# Teensy_Board_Connectors.net
KiCad netlist of a schematic drawn in EAGLE
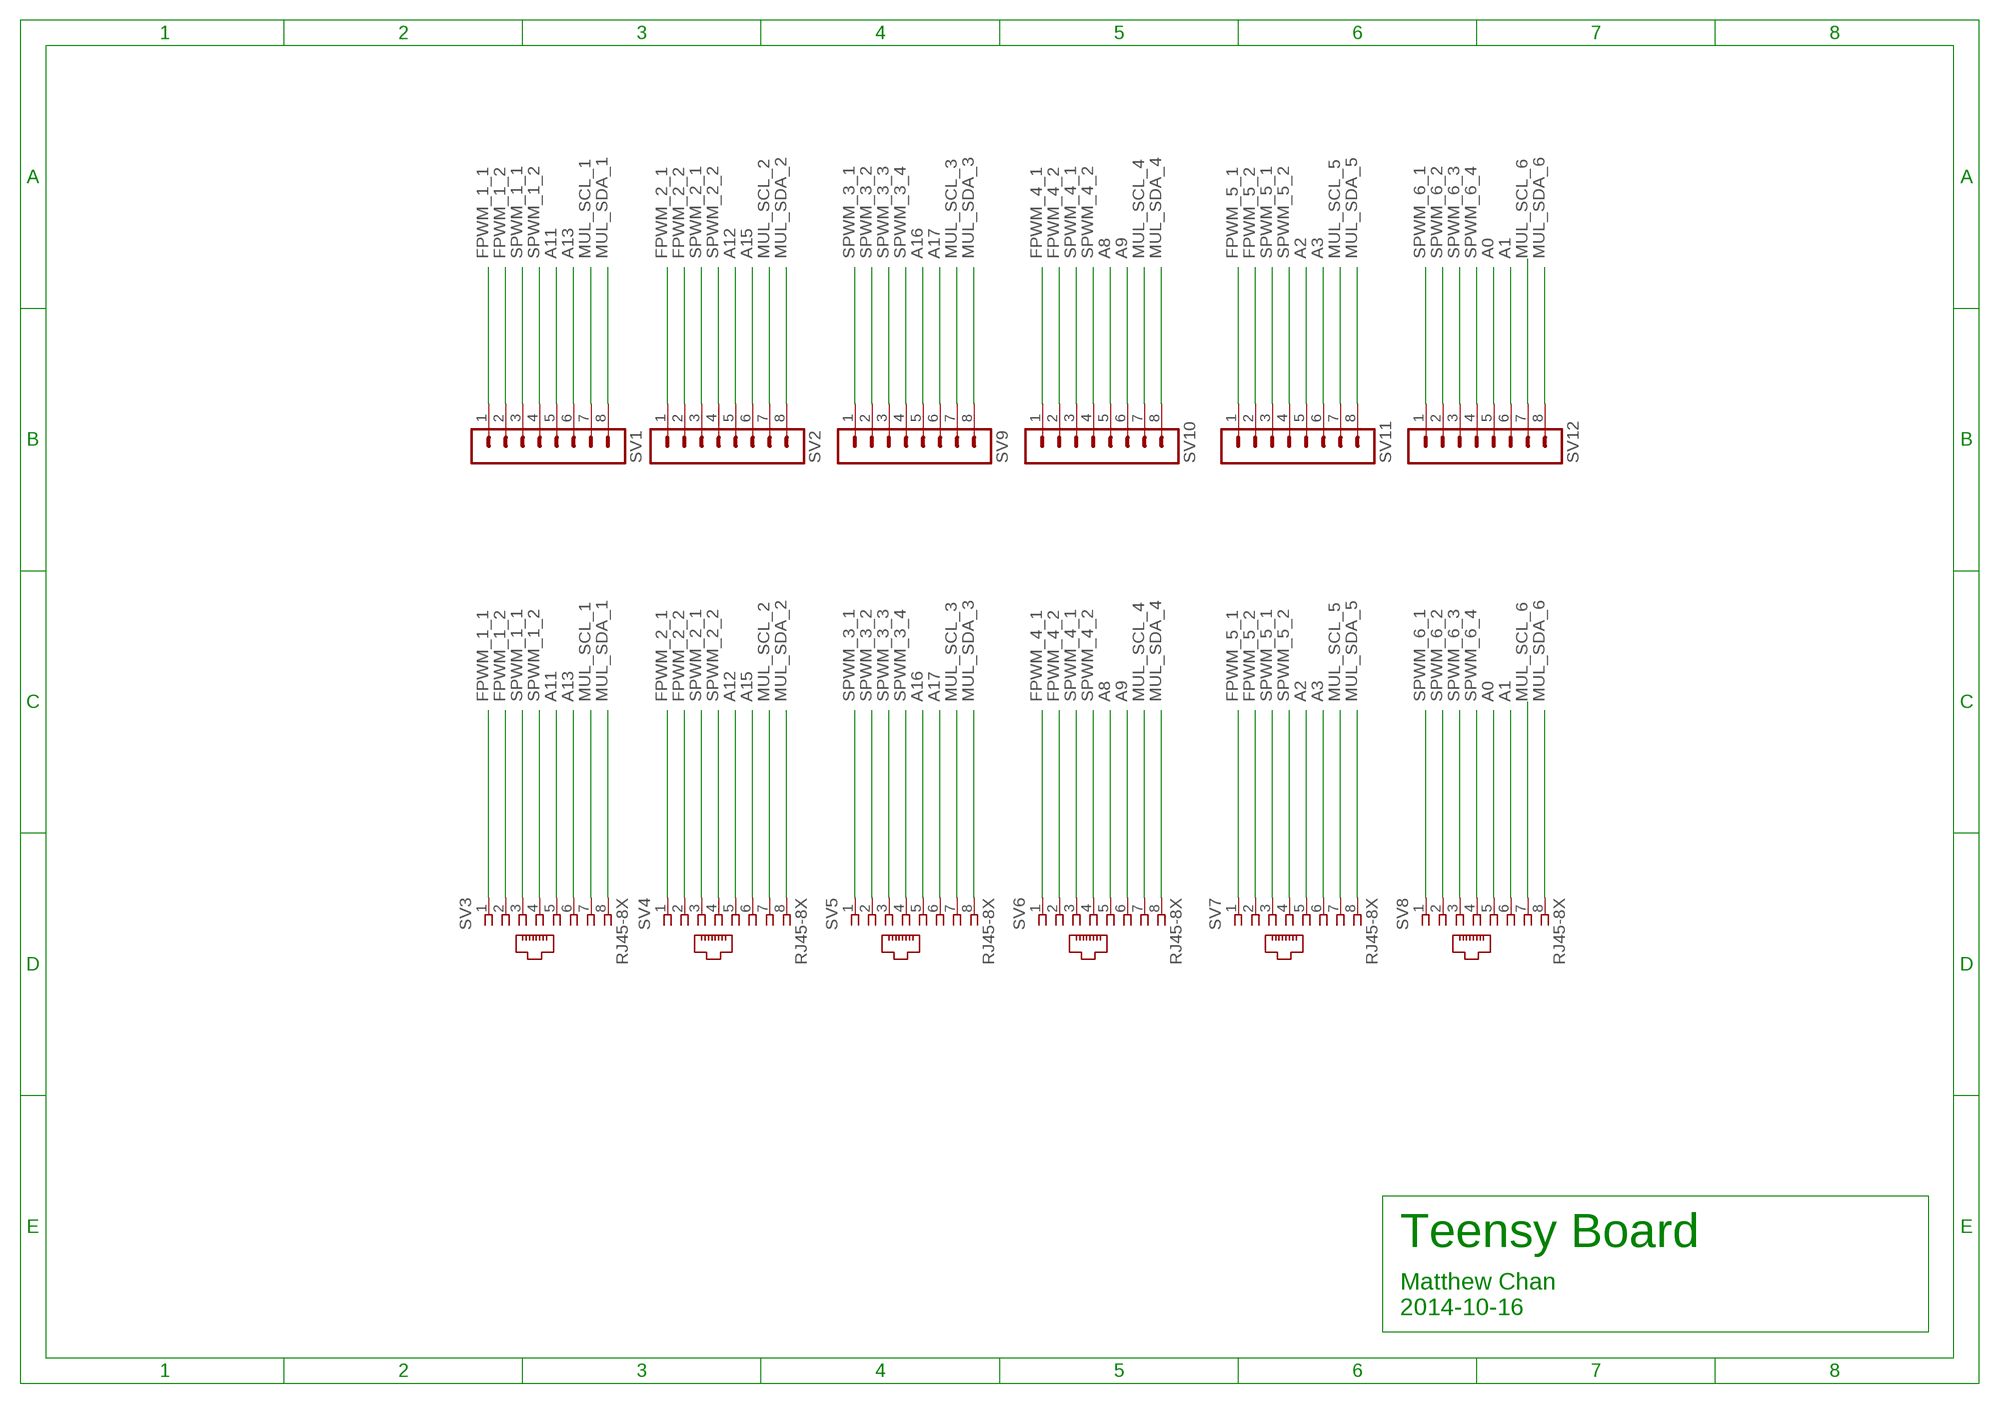
[diagram p0: schematic, sheet 1]

(export (version "E")
  (design (tool "Eeschema 10.0.6"))
  (components
    (comp (ref "SV1")
      (value "MA08-1")
      (footprint "eagle-import:MA08-1")
      (libsource (lib "eagle-import") (part "MA08-1"))
    )
    (comp (ref "SV2")
      (value "MA08-1")
      (footprint "eagle-import:MA08-1")
      (libsource (lib "eagle-import") (part "MA08-1"))
    )
    (comp (ref "SV3")
      (value "RJ45-8X")
      (footprint "eagle-import:RJ45-NO-SHIELD")
      (libsource (lib "eagle-import") (part "RJ45-8X"))
    )
    (comp (ref "SV4")
      (value "RJ45-8X")
      (footprint "eagle-import:RJ45-NO-SHIELD")
      (libsource (lib "eagle-import") (part "RJ45-8X"))
    )
    (comp (ref "SV5")
      (value "RJ45-8X")
      (footprint "eagle-import:RJ45-NO-SHIELD")
      (libsource (lib "eagle-import") (part "RJ45-8X"))
    )
    (comp (ref "SV6")
      (value "RJ45-8X")
      (footprint "eagle-import:RJ45-NO-SHIELD")
      (libsource (lib "eagle-import") (part "RJ45-8X"))
    )
    (comp (ref "SV7")
      (value "RJ45-8X")
      (footprint "eagle-import:RJ45-NO-SHIELD")
      (libsource (lib "eagle-import") (part "RJ45-8X"))
    )
    (comp (ref "SV8")
      (value "RJ45-8X")
      (footprint "eagle-import:RJ45-NO-SHIELD")
      (libsource (lib "eagle-import") (part "RJ45-8X"))
    )
    (comp (ref "SV9")
      (value "MA08-1")
      (footprint "eagle-import:MA08-1")
      (libsource (lib "eagle-import") (part "MA08-1"))
    )
    (comp (ref "SV10")
      (value "MA08-1")
      (footprint "eagle-import:MA08-1")
      (libsource (lib "eagle-import") (part "MA08-1"))
    )
    (comp (ref "SV11")
      (value "MA08-1")
      (footprint "eagle-import:MA08-1")
      (libsource (lib "eagle-import") (part "MA08-1"))
    )
    (comp (ref "SV12")
      (value "MA08-1")
      (footprint "eagle-import:MA08-1")
      (libsource (lib "eagle-import") (part "MA08-1"))
    )
  )
  (nets
    (net (code "1") (name "/A0") (class "Default")
      (node (ref "SV12") (pin "5") (pinfunction "5_5") (pintype "passive"))
      (node (ref "SV8") (pin "5") (pinfunction "5_5") (pintype "passive"))
    )
    (net (code "2") (name "/A1") (class "Default")
      (node (ref "SV12") (pin "6") (pinfunction "6_6") (pintype "passive"))
      (node (ref "SV8") (pin "6") (pinfunction "6_6") (pintype "passive"))
    )
    (net (code "3") (name "/A2") (class "Default")
      (node (ref "SV11") (pin "5") (pinfunction "5_5") (pintype "passive"))
      (node (ref "SV7") (pin "5") (pinfunction "5_5") (pintype "passive"))
    )
    (net (code "4") (name "/A3") (class "Default")
      (node (ref "SV11") (pin "6") (pinfunction "6_6") (pintype "passive"))
      (node (ref "SV7") (pin "6") (pinfunction "6_6") (pintype "passive"))
    )
    (net (code "5") (name "/A8") (class "Default")
      (node (ref "SV10") (pin "5") (pinfunction "5_5") (pintype "passive"))
      (node (ref "SV6") (pin "5") (pinfunction "5_5") (pintype "passive"))
    )
    (net (code "6") (name "/A9") (class "Default")
      (node (ref "SV10") (pin "6") (pinfunction "6_6") (pintype "passive"))
      (node (ref "SV6") (pin "6") (pinfunction "6_6") (pintype "passive"))
    )
    (net (code "7") (name "/A11") (class "Default")
      (node (ref "SV1") (pin "5") (pinfunction "5_5") (pintype "passive"))
      (node (ref "SV3") (pin "5") (pinfunction "5_5") (pintype "passive"))
    )
    (net (code "8") (name "/A12") (class "Default")
      (node (ref "SV2") (pin "5") (pinfunction "5_5") (pintype "passive"))
      (node (ref "SV4") (pin "5") (pinfunction "5_5") (pintype "passive"))
    )
    (net (code "9") (name "/A13") (class "Default")
      (node (ref "SV1") (pin "6") (pinfunction "6_6") (pintype "passive"))
      (node (ref "SV3") (pin "6") (pinfunction "6_6") (pintype "passive"))
    )
    (net (code "10") (name "/A15") (class "Default")
      (node (ref "SV2") (pin "6") (pinfunction "6_6") (pintype "passive"))
      (node (ref "SV4") (pin "6") (pinfunction "6_6") (pintype "passive"))
    )
    (net (code "11") (name "/A16") (class "Default")
      (node (ref "SV5") (pin "5") (pinfunction "5_5") (pintype "passive"))
      (node (ref "SV9") (pin "5") (pinfunction "5_5") (pintype "passive"))
    )
    (net (code "12") (name "/A17") (class "Default")
      (node (ref "SV5") (pin "6") (pinfunction "6_6") (pintype "passive"))
      (node (ref "SV9") (pin "6") (pinfunction "6_6") (pintype "passive"))
    )
    (net (code "13") (name "/FPWM_1_1") (class "Default")
      (node (ref "SV1") (pin "1") (pinfunction "1_1") (pintype "passive"))
      (node (ref "SV3") (pin "1") (pinfunction "1_1") (pintype "passive"))
    )
    (net (code "14") (name "/FPWM_1_2") (class "Default")
      (node (ref "SV1") (pin "2") (pinfunction "2_2") (pintype "passive"))
      (node (ref "SV3") (pin "2") (pinfunction "2_2") (pintype "passive"))
    )
    (net (code "15") (name "/FPWM_2_1") (class "Default")
      (node (ref "SV2") (pin "1") (pinfunction "1_1") (pintype "passive"))
      (node (ref "SV4") (pin "1") (pinfunction "1_1") (pintype "passive"))
    )
    (net (code "16") (name "/FPWM_2_2") (class "Default")
      (node (ref "SV2") (pin "2") (pinfunction "2_2") (pintype "passive"))
      (node (ref "SV4") (pin "2") (pinfunction "2_2") (pintype "passive"))
    )
    (net (code "17") (name "/FPWM_4_1") (class "Default")
      (node (ref "SV10") (pin "1") (pinfunction "1_1") (pintype "passive"))
      (node (ref "SV6") (pin "1") (pinfunction "1_1") (pintype "passive"))
    )
    (net (code "18") (name "/FPWM_4_2") (class "Default")
      (node (ref "SV10") (pin "2") (pinfunction "2_2") (pintype "passive"))
      (node (ref "SV6") (pin "2") (pinfunction "2_2") (pintype "passive"))
    )
    (net (code "19") (name "/FPWM_5_1") (class "Default")
      (node (ref "SV11") (pin "1") (pinfunction "1_1") (pintype "passive"))
      (node (ref "SV7") (pin "1") (pinfunction "1_1") (pintype "passive"))
    )
    (net (code "20") (name "/FPWM_5_2") (class "Default")
      (node (ref "SV11") (pin "2") (pinfunction "2_2") (pintype "passive"))
      (node (ref "SV7") (pin "2") (pinfunction "2_2") (pintype "passive"))
    )
    (net (code "21") (name "/MUL_SCL_1") (class "Default")
      (node (ref "SV1") (pin "7") (pinfunction "7_7") (pintype "passive"))
      (node (ref "SV3") (pin "7") (pinfunction "7_7") (pintype "passive"))
    )
    (net (code "22") (name "/MUL_SCL_2") (class "Default")
      (node (ref "SV2") (pin "7") (pinfunction "7_7") (pintype "passive"))
      (node (ref "SV4") (pin "7") (pinfunction "7_7") (pintype "passive"))
    )
    (net (code "23") (name "/MUL_SCL_3") (class "Default")
      (node (ref "SV5") (pin "7") (pinfunction "7_7") (pintype "passive"))
      (node (ref "SV9") (pin "7") (pinfunction "7_7") (pintype "passive"))
    )
    (net (code "24") (name "/MUL_SCL_4") (class "Default")
      (node (ref "SV10") (pin "7") (pinfunction "7_7") (pintype "passive"))
      (node (ref "SV6") (pin "7") (pinfunction "7_7") (pintype "passive"))
    )
    (net (code "25") (name "/MUL_SCL_5") (class "Default")
      (node (ref "SV11") (pin "7") (pinfunction "7_7") (pintype "passive"))
      (node (ref "SV7") (pin "7") (pinfunction "7_7") (pintype "passive"))
    )
    (net (code "26") (name "/MUL_SCL_6") (class "Default")
      (node (ref "SV12") (pin "7") (pinfunction "7_7") (pintype "passive"))
      (node (ref "SV8") (pin "7") (pinfunction "7_7") (pintype "passive"))
    )
    (net (code "27") (name "/MUL_SDA_1") (class "Default")
      (node (ref "SV1") (pin "8") (pinfunction "8_8") (pintype "passive"))
      (node (ref "SV3") (pin "8") (pinfunction "8_8") (pintype "passive"))
    )
    (net (code "28") (name "/MUL_SDA_2") (class "Default")
      (node (ref "SV2") (pin "8") (pinfunction "8_8") (pintype "passive"))
      (node (ref "SV4") (pin "8") (pinfunction "8_8") (pintype "passive"))
    )
    (net (code "29") (name "/MUL_SDA_3") (class "Default")
      (node (ref "SV5") (pin "8") (pinfunction "8_8") (pintype "passive"))
      (node (ref "SV9") (pin "8") (pinfunction "8_8") (pintype "passive"))
    )
    (net (code "30") (name "/MUL_SDA_4") (class "Default")
      (node (ref "SV10") (pin "8") (pinfunction "8_8") (pintype "passive"))
      (node (ref "SV6") (pin "8") (pinfunction "8_8") (pintype "passive"))
    )
    (net (code "31") (name "/MUL_SDA_5") (class "Default")
      (node (ref "SV11") (pin "8") (pinfunction "8_8") (pintype "passive"))
      (node (ref "SV7") (pin "8") (pinfunction "8_8") (pintype "passive"))
    )
    (net (code "32") (name "/MUL_SDA_6") (class "Default")
      (node (ref "SV12") (pin "8") (pinfunction "8_8") (pintype "passive"))
      (node (ref "SV8") (pin "8") (pinfunction "8_8") (pintype "passive"))
    )
    (net (code "33") (name "/SPWM_1_1") (class "Default")
      (node (ref "SV1") (pin "3") (pinfunction "3_3") (pintype "passive"))
      (node (ref "SV3") (pin "3") (pinfunction "3_3") (pintype "passive"))
    )
    (net (code "34") (name "/SPWM_1_2") (class "Default")
      (node (ref "SV1") (pin "4") (pinfunction "4_4") (pintype "passive"))
      (node (ref "SV3") (pin "4") (pinfunction "4_4") (pintype "passive"))
    )
    (net (code "35") (name "/SPWM_2_1") (class "Default")
      (node (ref "SV2") (pin "3") (pinfunction "3_3") (pintype "passive"))
      (node (ref "SV4") (pin "3") (pinfunction "3_3") (pintype "passive"))
    )
    (net (code "36") (name "/SPWM_2_2") (class "Default")
      (node (ref "SV2") (pin "4") (pinfunction "4_4") (pintype "passive"))
      (node (ref "SV4") (pin "4") (pinfunction "4_4") (pintype "passive"))
    )
    (net (code "37") (name "/SPWM_3_1") (class "Default")
      (node (ref "SV5") (pin "1") (pinfunction "1_1") (pintype "passive"))
      (node (ref "SV9") (pin "1") (pinfunction "1_1") (pintype "passive"))
    )
    (net (code "38") (name "/SPWM_3_2") (class "Default")
      (node (ref "SV5") (pin "2") (pinfunction "2_2") (pintype "passive"))
      (node (ref "SV9") (pin "2") (pinfunction "2_2") (pintype "passive"))
    )
    (net (code "39") (name "/SPWM_3_3") (class "Default")
      (node (ref "SV5") (pin "3") (pinfunction "3_3") (pintype "passive"))
      (node (ref "SV9") (pin "3") (pinfunction "3_3") (pintype "passive"))
    )
    (net (code "40") (name "/SPWM_3_4") (class "Default")
      (node (ref "SV5") (pin "4") (pinfunction "4_4") (pintype "passive"))
      (node (ref "SV9") (pin "4") (pinfunction "4_4") (pintype "passive"))
    )
    (net (code "41") (name "/SPWM_4_1") (class "Default")
      (node (ref "SV10") (pin "3") (pinfunction "3_3") (pintype "passive"))
      (node (ref "SV6") (pin "3") (pinfunction "3_3") (pintype "passive"))
    )
    (net (code "42") (name "/SPWM_4_2") (class "Default")
      (node (ref "SV10") (pin "4") (pinfunction "4_4") (pintype "passive"))
      (node (ref "SV6") (pin "4") (pinfunction "4_4") (pintype "passive"))
    )
    (net (code "43") (name "/SPWM_5_1") (class "Default")
      (node (ref "SV11") (pin "3") (pinfunction "3_3") (pintype "passive"))
      (node (ref "SV7") (pin "3") (pinfunction "3_3") (pintype "passive"))
    )
    (net (code "44") (name "/SPWM_5_2") (class "Default")
      (node (ref "SV11") (pin "4") (pinfunction "4_4") (pintype "passive"))
      (node (ref "SV7") (pin "4") (pinfunction "4_4") (pintype "passive"))
    )
    (net (code "45") (name "/SPWM_6_1") (class "Default")
      (node (ref "SV12") (pin "1") (pinfunction "1_1") (pintype "passive"))
      (node (ref "SV8") (pin "1") (pinfunction "1_1") (pintype "passive"))
    )
    (net (code "46") (name "/SPWM_6_2") (class "Default")
      (node (ref "SV12") (pin "2") (pinfunction "2_2") (pintype "passive"))
      (node (ref "SV8") (pin "2") (pinfunction "2_2") (pintype "passive"))
    )
    (net (code "47") (name "/SPWM_6_3") (class "Default")
      (node (ref "SV12") (pin "3") (pinfunction "3_3") (pintype "passive"))
      (node (ref "SV8") (pin "3") (pinfunction "3_3") (pintype "passive"))
    )
    (net (code "48") (name "/SPWM_6_4") (class "Default")
      (node (ref "SV12") (pin "4") (pinfunction "4_4") (pintype "passive"))
      (node (ref "SV8") (pin "4") (pinfunction "4_4") (pintype "passive"))
    )
  )
)
